# riffleito-THPL-revA.net
KiCad netlist of a schematic drawn in EAGLE
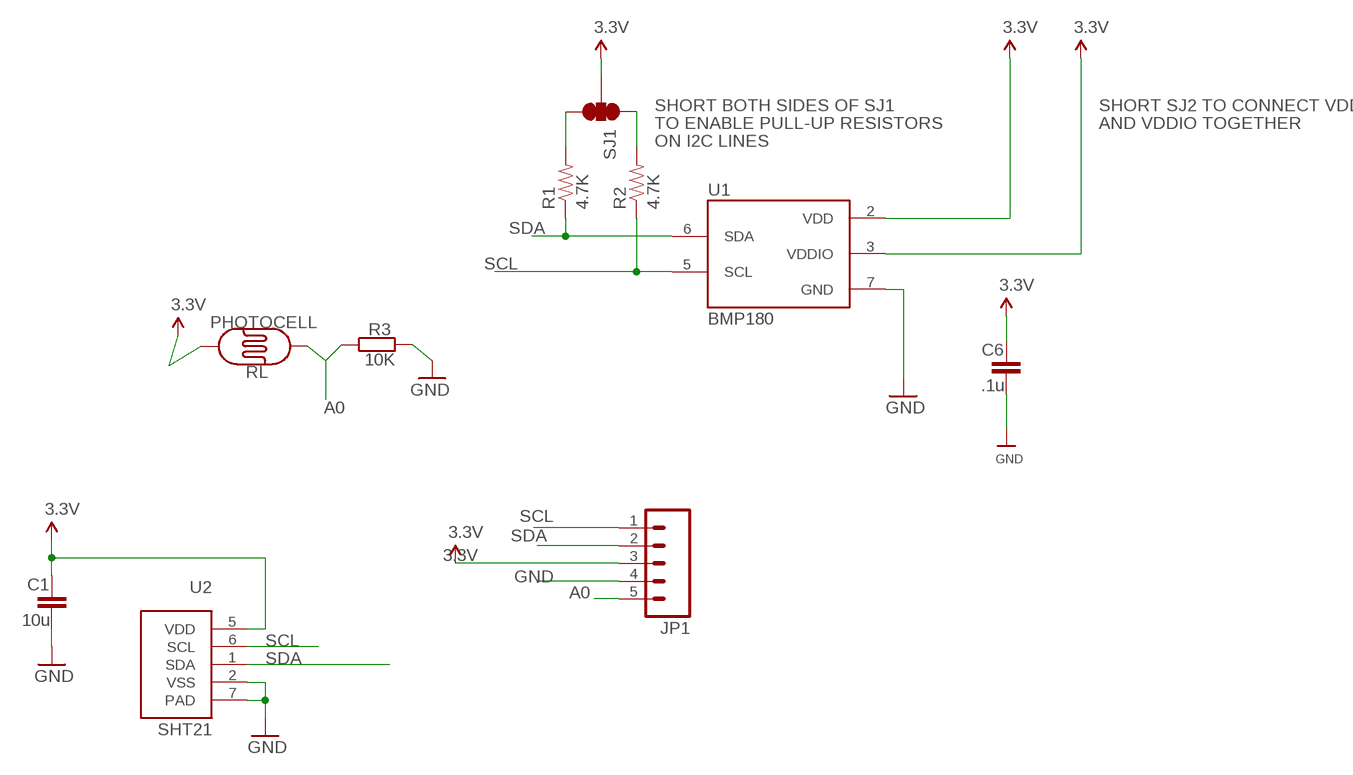
[diagram p0: schematic, sheet 1]

(export (version "E")
  (design (tool "Eeschema 10.0.6"))
  (components
    (comp (ref "C1")
      (value "10u")
      (footprint "eagle-import:C0805")
      (libsource (lib "eagle-import") (part "C-EUC0805"))
    )
    (comp (ref "C6")
      (value ".1u")
      (footprint "eagle-import:C0805")
      (libsource (lib "eagle-import") (part "C-EUC0805"))
    )
    (comp (ref "JP1")
      (value "M05PTH")
      (footprint "eagle-import:1X05")
      (libsource (lib "eagle-import") (part "M05PTH"))
    )
    (comp (ref "R1")
      (value "4.7K")
      (footprint "eagle-import:0603-RES")
      (libsource (lib "eagle-import") (part "RESISTOR0603-RES"))
    )
    (comp (ref "R2")
      (value "4.7K")
      (footprint "eagle-import:0603-RES")
      (libsource (lib "eagle-import") (part "RESISTOR0603-RES"))
    )
    (comp (ref "R3")
      (value "10K")
      (footprint "eagle-import:R0805")
      (libsource (lib "eagle-import") (part "R-EU_R0805"))
    )
    (comp (ref "RL")
      (value "PHOTOCELL")
      (footprint "eagle-import:PHOTOCELL")
      (libsource (lib "eagle-import") (part "PHOTOCELLPTH"))
    )
    (comp (ref "SJ1")
      (value "SOLDERJUMPER_2WAYPASTE1&2&3")
      (footprint "eagle-import:SJ_3_PASTE1&2&3")
      (libsource (lib "eagle-import") (part "SOLDERJUMPER_2WAYPASTE1&2&3"))
    )
    (comp (ref "U1")
      (value "BMP180")
      (footprint "eagle-import:BMP180")
      (libsource (lib "eagle-import") (part "BMP180"))
    )
    (comp (ref "U2")
      (value "SHT21")
      (footprint "eagle-import:SEN-SENSIRION-SHT2X")
      (libsource (lib "eagle-import") (part "SEN-SENSIRION-SHT2X"))
    )
  )
  (nets
    (net (code "1") (name "/A0") (class "Default")
      (node (ref "JP1") (pin "5") (pinfunction "5_5") (pintype "passive"))
      (node (ref "R3") (pin "1") (pinfunction "1_1") (pintype "passive"))
      (node (ref "RL") (pin "1") (pinfunction "P$1_1") (pintype "bidirectional"))
    )
    (net (code "2") (name "/SCL") (class "Default")
      (node (ref "JP1") (pin "1") (pinfunction "1_1") (pintype "passive"))
      (node (ref "R2") (pin "1") (pinfunction "1_1") (pintype "passive"))
      (node (ref "U1") (pin "5") (pinfunction "SCL_5") (pintype "input"))
      (node (ref "U2") (pin "6") (pinfunction "SCL_6") (pintype "bidirectional"))
    )
    (net (code "3") (name "/SDA") (class "Default")
      (node (ref "JP1") (pin "2") (pinfunction "2_2") (pintype "passive"))
      (node (ref "R1") (pin "1") (pinfunction "1_1") (pintype "passive"))
      (node (ref "U1") (pin "6") (pinfunction "SDA_6") (pintype "bidirectional"))
      (node (ref "U2") (pin "1") (pinfunction "SDA_1") (pintype "bidirectional"))
    )
    (net (code "4") (name "3.3V") (class "Default")
      (node (ref "C1") (pin "1") (pinfunction "1_1") (pintype "passive"))
      (node (ref "C6") (pin "1") (pinfunction "1_1") (pintype "passive"))
      (node (ref "JP1") (pin "3") (pinfunction "3_3") (pintype "passive"))
      (node (ref "RL") (pin "2") (pinfunction "P$2_2") (pintype "bidirectional"))
      (node (ref "SJ1") (pin "2") (pinfunction "2_2") (pintype "passive"))
      (node (ref "U1") (pin "2") (pinfunction "VDD_2") (pintype "power_in"))
      (node (ref "U1") (pin "3") (pinfunction "VDDIO_3") (pintype "power_in"))
      (node (ref "U2") (pin "5") (pinfunction "VDD_5") (pintype "bidirectional"))
    )
    (net (code "5") (name "GND") (class "Default")
      (node (ref "C1") (pin "2") (pinfunction "2_2") (pintype "passive"))
      (node (ref "C6") (pin "2") (pinfunction "2_2") (pintype "passive"))
      (node (ref "JP1") (pin "4") (pinfunction "4_4") (pintype "passive"))
      (node (ref "R3") (pin "2") (pinfunction "2_2") (pintype "passive"))
      (node (ref "U1") (pin "7") (pinfunction "GND_7") (pintype "power_in"))
      (node (ref "U2") (pin "2") (pinfunction "VSS_2") (pintype "bidirectional"))
      (node (ref "U2") (pin "7") (pinfunction "PAD_7") (pintype "bidirectional"))
    )
    (net (code "6") (name "Net-(R1-Pad2)") (class "Default")
      (node (ref "R1") (pin "2") (pinfunction "2_2") (pintype "passive"))
      (node (ref "SJ1") (pin "3") (pinfunction "3_3") (pintype "passive"))
    )
    (net (code "7") (name "Net-(R2-Pad2)") (class "Default")
      (node (ref "R2") (pin "2") (pinfunction "2_2") (pintype "passive"))
      (node (ref "SJ1") (pin "1") (pinfunction "1_1") (pintype "passive"))
    )
  )
)
